# CocoMake7_SMD.net
KiCad netlist of a schematic drawn in EAGLE
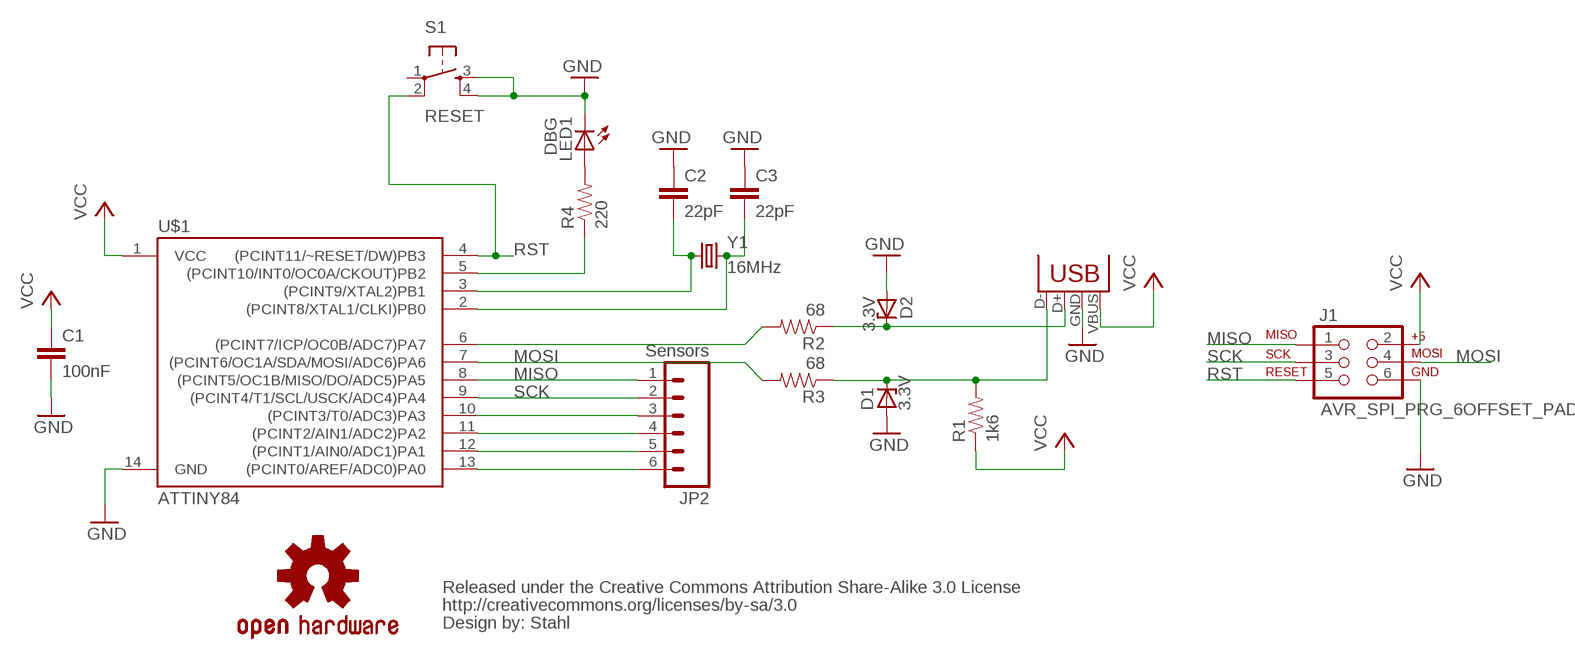
[diagram p0: schematic, sheet 1]

(export (version "E")
  (design (tool "Eeschema 10.0.6"))
  (components
    (comp (ref "C1")
      (value "100nF")
      (footprint "eagle-import:1206")
      (libsource (lib "eagle-import") (part "CAP1206"))
    )
    (comp (ref "C2")
      (value "22pF")
      (footprint "eagle-import:1206")
      (libsource (lib "eagle-import") (part "CAP1206"))
    )
    (comp (ref "C3")
      (value "22pF")
      (footprint "eagle-import:1206")
      (libsource (lib "eagle-import") (part "CAP1206"))
    )
    (comp (ref "CC_TEXT1")
      (value "CREATIVE_COMMONS")
      (footprint "eagle-import:CREATIVE_COMMONS")
      (libsource (lib "eagle-import") (part "CREATIVE_COMMONS"))
    )
    (comp (ref "D1")
      (value "3.3V")
      (footprint "eagle-import:SOD80C")
      (libsource (lib "eagle-import") (part "ZENER-DIODESOD80C"))
    )
    (comp (ref "D2")
      (value "3.3V")
      (footprint "eagle-import:SOD80C")
      (libsource (lib "eagle-import") (part "ZENER-DIODESOD80C"))
    )
    (comp (ref "J1")
      (value "AVR_SPI_PRG_6OFFSET_PADS")
      (footprint "eagle-import:2X3_OFFSET")
      (libsource (lib "eagle-import") (part "AVR_SPI_PRG_6OFFSET_PADS"))
    )
    (comp (ref "JP1")
      (value "USB-A-H")
      (footprint "eagle-import:USB-A-H")
      (libsource (lib "eagle-import") (part "USB-A-H"))
    )
    (comp (ref "JP2")
      (value "Sensors")
      (footprint "eagle-import:1X06_LONGPADS")
      (libsource (lib "eagle-import") (part "M06LONGPADS"))
    )
    (comp (ref "LED1")
      (value "DBG")
      (footprint "eagle-import:LED-1206")
      (libsource (lib "eagle-import") (part "LED1206"))
    )
    (comp (ref "LOGO1")
      (value "OSHW-LOGOS")
      (footprint "eagle-import:OSHW-LOGO-S")
      (libsource (lib "eagle-import") (part "OSHW-LOGOS"))
    )
    (comp (ref "R1")
      (value "1k6")
      (footprint "eagle-import:1206")
      (libsource (lib "eagle-import") (part "RESISTOR1206"))
    )
    (comp (ref "R2")
      (value "68")
      (footprint "eagle-import:1206")
      (libsource (lib "eagle-import") (part "RESISTOR1206"))
    )
    (comp (ref "R3")
      (value "68")
      (footprint "eagle-import:1206")
      (libsource (lib "eagle-import") (part "RESISTOR1206"))
    )
    (comp (ref "R4")
      (value "220")
      (footprint "eagle-import:1206")
      (libsource (lib "eagle-import") (part "RESISTOR1206"))
    )
    (comp (ref "S1")
      (value "RESET")
      (footprint "eagle-import:TACTILE_SWITCH_SMD")
      (libsource (lib "eagle-import") (part "TAC_SWITCHSMD"))
    )
    (comp (ref "U$1")
      (value "ATTINY84")
      (footprint "eagle-import:SO14")
      (libsource (lib "eagle-import") (part "ATTINY84"))
    )
    (comp (ref "Y1")
      (value "16MHz")
      (footprint "eagle-import:HC49UP")
      (libsource (lib "eagle-import") (part "CRYSTALSMD"))
    )
  )
  (nets
    (net (code "1") (name "/MISO") (class "Default")
      (node (ref "J1") (pin "1") (pinfunction "1_1") (pintype "passive"))
      (node (ref "JP2") (pin "1") (pinfunction "1_1") (pintype "passive"))
      (node (ref "U$1") (pin "8") (pinfunction "(PCINT5/OC1B/MISO/DO/ADC5)PA5_8") (pintype "bidirectional"))
    )
    (net (code "2") (name "/MOSI") (class "Default")
      (node (ref "J1") (pin "4") (pinfunction "4_4") (pintype "passive"))
      (node (ref "R3") (pin "2") (pinfunction "2_2") (pintype "passive"))
      (node (ref "U$1") (pin "7") (pinfunction "(PCINT6/OC1A/SDA/MOSI/ADC6)PA6_7") (pintype "bidirectional"))
    )
    (net (code "3") (name "/RST") (class "Default")
      (node (ref "J1") (pin "5") (pinfunction "5_5") (pintype "passive"))
      (node (ref "S1") (pin "2") (pinfunction "2_2") (pintype "passive"))
      (node (ref "U$1") (pin "4") (pinfunction "(PCINT11/~{RESET/DW})PB3_4") (pintype "bidirectional"))
    )
    (net (code "4") (name "/SCK") (class "Default")
      (node (ref "J1") (pin "3") (pinfunction "3_3") (pintype "passive"))
      (node (ref "JP2") (pin "2") (pinfunction "2_2") (pintype "passive"))
      (node (ref "U$1") (pin "9") (pinfunction "(PCINT4/T1/SCL/USCK/ADC4)PA4_9") (pintype "bidirectional"))
    )
    (net (code "5") (name "GND") (class "Default")
      (node (ref "C1") (pin "2") (pinfunction "2_2") (pintype "passive"))
      (node (ref "C2") (pin "1") (pinfunction "1_1") (pintype "passive"))
      (node (ref "C3") (pin "1") (pinfunction "1_1") (pintype "passive"))
      (node (ref "D1") (pin "A") (pinfunction "A_A") (pintype "passive"))
      (node (ref "D2") (pin "A") (pinfunction "A_A") (pintype "passive"))
      (node (ref "J1") (pin "6") (pinfunction "6_6") (pintype "passive"))
      (node (ref "JP1") (pin "GND") (pinfunction "VBUS_GND") (pintype "bidirectional"))
      (node (ref "LED1") (pin "C") (pinfunction "C_C") (pintype "passive"))
      (node (ref "S1") (pin "3") (pinfunction "3_3") (pintype "passive"))
      (node (ref "S1") (pin "4") (pinfunction "4_4") (pintype "passive"))
      (node (ref "U$1") (pin "14") (pinfunction "GND_14") (pintype "bidirectional"))
    )
    (net (code "6") (name "Net-(JP1-D+)") (class "Default")
      (node (ref "D1") (pin "C") (pinfunction "C_C") (pintype "passive"))
      (node (ref "JP1") (pin "D-") (pinfunction "D+_D-") (pintype "bidirectional"))
      (node (ref "R1") (pin "2") (pinfunction "2_2") (pintype "passive"))
      (node (ref "R3") (pin "1") (pinfunction "1_1") (pintype "passive"))
    )
    (net (code "7") (name "Net-(JP1-D-)") (class "Default")
      (node (ref "D2") (pin "C") (pinfunction "C_C") (pintype "passive"))
      (node (ref "JP1") (pin "D+") (pinfunction "D-_D+") (pintype "bidirectional"))
      (node (ref "R2") (pin "1") (pinfunction "1_1") (pintype "passive"))
    )
    (net (code "8") (name "Net-(LED1-PadA)") (class "Default")
      (node (ref "LED1") (pin "A") (pinfunction "A_A") (pintype "passive"))
      (node (ref "R4") (pin "2") (pinfunction "2_2") (pintype "passive"))
    )
    (net (code "9") (name "Net-(U$1-(PCINT0{slash}AREF{slash}ADC0)PA0)") (class "Default")
      (node (ref "JP2") (pin "6") (pinfunction "6_6") (pintype "passive"))
      (node (ref "U$1") (pin "13") (pinfunction "(PCINT0/AREF/ADC0)PA0_13") (pintype "bidirectional"))
    )
    (net (code "10") (name "Net-(U$1-(PCINT1{slash}AIN0{slash}ADC1)PA1)") (class "Default")
      (node (ref "JP2") (pin "5") (pinfunction "5_5") (pintype "passive"))
      (node (ref "U$1") (pin "12") (pinfunction "(PCINT1/AIN0/ADC1)PA1_12") (pintype "bidirectional"))
    )
    (net (code "11") (name "Net-(U$1-(PCINT2{slash}AIN1{slash}ADC2)PA2)") (class "Default")
      (node (ref "JP2") (pin "4") (pinfunction "4_4") (pintype "passive"))
      (node (ref "U$1") (pin "11") (pinfunction "(PCINT2/AIN1/ADC2)PA2_11") (pintype "bidirectional"))
    )
    (net (code "12") (name "Net-(U$1-(PCINT3{slash}T0{slash}ADC3)PA3)") (class "Default")
      (node (ref "JP2") (pin "3") (pinfunction "3_3") (pintype "passive"))
      (node (ref "U$1") (pin "10") (pinfunction "(PCINT3/T0/ADC3)PA3_10") (pintype "bidirectional"))
    )
    (net (code "13") (name "Net-(U$1-(PCINT7{slash}ICP{slash}OC0B{slash}ADC7)PA7)") (class "Default")
      (node (ref "R2") (pin "2") (pinfunction "2_2") (pintype "passive"))
      (node (ref "U$1") (pin "6") (pinfunction "(PCINT7/ICP/OC0B/ADC7)PA7_6") (pintype "bidirectional"))
    )
    (net (code "14") (name "Net-(U$1-(PCINT8{slash}XTAL1{slash}CLKI)PB0)") (class "Default")
      (node (ref "C3") (pin "2") (pinfunction "2_2") (pintype "passive"))
      (node (ref "U$1") (pin "2") (pinfunction "(PCINT8/XTAL1/CLKI)PB0_2") (pintype "bidirectional"))
      (node (ref "Y1") (pin "2") (pinfunction "2_2") (pintype "passive"))
    )
    (net (code "15") (name "Net-(U$1-(PCINT9{slash}XTAL2)PB1)") (class "Default")
      (node (ref "C2") (pin "2") (pinfunction "2_2") (pintype "passive"))
      (node (ref "U$1") (pin "3") (pinfunction "(PCINT9/XTAL2)PB1_3") (pintype "bidirectional"))
      (node (ref "Y1") (pin "1") (pinfunction "1_1") (pintype "passive"))
    )
    (net (code "16") (name "Net-(U$1-(PCINT10{slash}INT0{slash}OC0A{slash}CKOUT)PB2)") (class "Default")
      (node (ref "R4") (pin "1") (pinfunction "1_1") (pintype "passive"))
      (node (ref "U$1") (pin "5") (pinfunction "(PCINT10/INT0/OC0A/CKOUT)PB2_5") (pintype "bidirectional"))
    )
    (net (code "17") (name "VCC") (class "Default")
      (node (ref "C1") (pin "1") (pinfunction "1_1") (pintype "passive"))
      (node (ref "J1") (pin "2") (pinfunction "2_2") (pintype "passive"))
      (node (ref "JP1") (pin "VBUS") (pinfunction "GND_VBUS") (pintype "bidirectional"))
      (node (ref "R1") (pin "1") (pinfunction "1_1") (pintype "passive"))
      (node (ref "U$1") (pin "1") (pinfunction "VCC_1") (pintype "bidirectional"))
    )
    (net (code "18") (name "unconnected-(S1-Pad1)") (class "Default")
      (node (ref "S1") (pin "1") (pinfunction "1_1") (pintype "passive"))
    )
  )
)
